# main.net
KiCad netlist of a schematic drawn in EAGLE
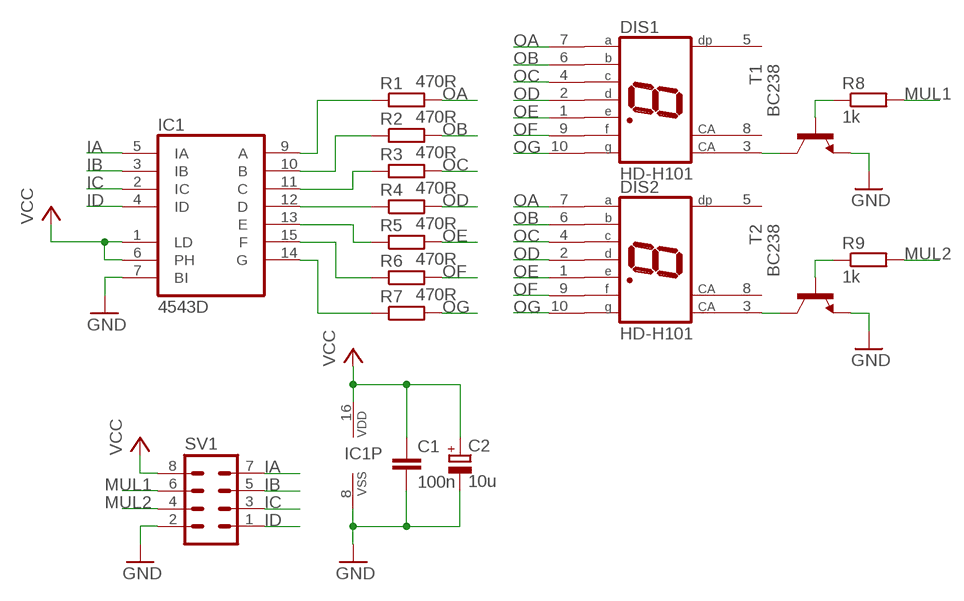
[diagram p0: schematic, sheet 1]

(export (version "E")
  (design (tool "Eeschema 10.0.6"))
  (components
    (comp (ref "C1")
      (value "100n")
      (footprint "eagle-import:C1206")
      (libsource (lib "eagle-import") (part "C-EUC1206"))
    )
    (comp (ref "C2")
      (value "10u")
      (footprint "eagle-import:SMC_A")
      (libsource (lib "eagle-import") (part "CPOL-EUSMCA"))
    )
    (comp (ref "DIS1")
      (value "HD-H101")
      (footprint "eagle-import:HDSP-M")
      (libsource (lib "eagle-import") (part "HD-H101"))
    )
    (comp (ref "DIS2")
      (value "HD-H101")
      (footprint "eagle-import:HDSP-M")
      (libsource (lib "eagle-import") (part "HD-H101"))
    )
    (comp (ref "IC1")
      (value "4543D")
      (footprint "eagle-import:SO16")
      (libsource (lib "eagle-import") (part "4543D"))
    )
    (comp (ref "R1")
      (value "470R")
      (footprint "eagle-import:R1206")
      (libsource (lib "eagle-import") (part "R-EU_R1206"))
    )
    (comp (ref "R2")
      (value "470R")
      (footprint "eagle-import:R1206")
      (libsource (lib "eagle-import") (part "R-EU_R1206"))
    )
    (comp (ref "R3")
      (value "470R")
      (footprint "eagle-import:R1206")
      (libsource (lib "eagle-import") (part "R-EU_R1206"))
    )
    (comp (ref "R4")
      (value "470R")
      (footprint "eagle-import:R1206")
      (libsource (lib "eagle-import") (part "R-EU_R1206"))
    )
    (comp (ref "R5")
      (value "470R")
      (footprint "eagle-import:R1206")
      (libsource (lib "eagle-import") (part "R-EU_R1206"))
    )
    (comp (ref "R6")
      (value "470R")
      (footprint "eagle-import:R1206")
      (libsource (lib "eagle-import") (part "R-EU_R1206"))
    )
    (comp (ref "R7")
      (value "470R")
      (footprint "eagle-import:R1206")
      (libsource (lib "eagle-import") (part "R-EU_R1206"))
    )
    (comp (ref "R8")
      (value "1k")
      (footprint "eagle-import:R1206")
      (libsource (lib "eagle-import") (part "R-EU_R1206"))
    )
    (comp (ref "R9")
      (value "1k")
      (footprint "eagle-import:R1206")
      (libsource (lib "eagle-import") (part "R-EU_R1206"))
    )
    (comp (ref "SV1")
      (value "MA04-2")
      (footprint "eagle-import:MA04-2")
      (libsource (lib "eagle-import") (part "MA04-2"))
    )
    (comp (ref "T1")
      (value "BC238")
      (footprint "eagle-import:TO92")
      (libsource (lib "eagle-import") (part "BC238"))
    )
    (comp (ref "T2")
      (value "BC238")
      (footprint "eagle-import:TO92")
      (libsource (lib "eagle-import") (part "BC238"))
    )
  )
  (nets
    (net (code "1") (name "/IA") (class "Default")
      (node (ref "IC1") (pin "5") (pinfunction "IA_5") (pintype "input"))
      (node (ref "SV1") (pin "7") (pinfunction "7_7") (pintype "passive"))
    )
    (net (code "2") (name "/IB") (class "Default")
      (node (ref "IC1") (pin "3") (pinfunction "IB_3") (pintype "input"))
      (node (ref "SV1") (pin "5") (pinfunction "5_5") (pintype "passive"))
    )
    (net (code "3") (name "/IC") (class "Default")
      (node (ref "IC1") (pin "2") (pinfunction "IC_2") (pintype "input"))
      (node (ref "SV1") (pin "3") (pinfunction "3_3") (pintype "passive"))
    )
    (net (code "4") (name "/ID") (class "Default")
      (node (ref "IC1") (pin "4") (pinfunction "ID_4") (pintype "input"))
      (node (ref "SV1") (pin "1") (pinfunction "1_1") (pintype "passive"))
    )
    (net (code "5") (name "/MUL1") (class "Default")
      (node (ref "R8") (pin "2") (pinfunction "2_2") (pintype "passive"))
      (node (ref "SV1") (pin "6") (pinfunction "6_6") (pintype "passive"))
    )
    (net (code "6") (name "/MUL2") (class "Default")
      (node (ref "R9") (pin "2") (pinfunction "2_2") (pintype "passive"))
      (node (ref "SV1") (pin "4") (pinfunction "4_4") (pintype "passive"))
    )
    (net (code "7") (name "/OA") (class "Default")
      (node (ref "DIS1") (pin "7") (pinfunction "A_7") (pintype "passive"))
      (node (ref "DIS2") (pin "7") (pinfunction "A_7") (pintype "passive"))
      (node (ref "R1") (pin "2") (pinfunction "2_2") (pintype "passive"))
    )
    (net (code "8") (name "/OB") (class "Default")
      (node (ref "DIS1") (pin "6") (pinfunction "B_6") (pintype "passive"))
      (node (ref "DIS2") (pin "6") (pinfunction "B_6") (pintype "passive"))
      (node (ref "R2") (pin "2") (pinfunction "2_2") (pintype "passive"))
    )
    (net (code "9") (name "/OC") (class "Default")
      (node (ref "DIS1") (pin "4") (pinfunction "C_4") (pintype "passive"))
      (node (ref "DIS2") (pin "4") (pinfunction "C_4") (pintype "passive"))
      (node (ref "R3") (pin "2") (pinfunction "2_2") (pintype "passive"))
    )
    (net (code "10") (name "/OD") (class "Default")
      (node (ref "DIS1") (pin "2") (pinfunction "D_2") (pintype "passive"))
      (node (ref "DIS2") (pin "2") (pinfunction "D_2") (pintype "passive"))
      (node (ref "R4") (pin "2") (pinfunction "2_2") (pintype "passive"))
    )
    (net (code "11") (name "/OE") (class "Default")
      (node (ref "DIS1") (pin "1") (pinfunction "E_1") (pintype "passive"))
      (node (ref "DIS2") (pin "1") (pinfunction "E_1") (pintype "passive"))
      (node (ref "R5") (pin "2") (pinfunction "2_2") (pintype "passive"))
    )
    (net (code "12") (name "/OF") (class "Default")
      (node (ref "DIS1") (pin "9") (pinfunction "F_9") (pintype "passive"))
      (node (ref "DIS2") (pin "9") (pinfunction "F_9") (pintype "passive"))
      (node (ref "R6") (pin "2") (pinfunction "2_2") (pintype "passive"))
    )
    (net (code "13") (name "/OG") (class "Default")
      (node (ref "DIS1") (pin "10") (pinfunction "G_10") (pintype "passive"))
      (node (ref "DIS2") (pin "10") (pinfunction "G_10") (pintype "passive"))
      (node (ref "R7") (pin "2") (pinfunction "2_2") (pintype "passive"))
    )
    (net (code "14") (name "GND") (class "Default")
      (node (ref "C1") (pin "2") (pinfunction "2_2") (pintype "passive"))
      (node (ref "C2") (pin "-") (pinfunction "-_-") (pintype "passive"))
      (node (ref "IC1") (pin "7") (pinfunction "BI_7") (pintype "input"))
      (node (ref "IC1") (pin "8") (pinfunction "VSS_8") (pintype "power_in"))
      (node (ref "SV1") (pin "2") (pinfunction "2_2") (pintype "passive"))
      (node (ref "T1") (pin "1") (pinfunction "E_1") (pintype "passive"))
      (node (ref "T2") (pin "1") (pinfunction "E_1") (pintype "passive"))
    )
    (net (code "15") (name "Net-(IC1A-A)") (class "Default")
      (node (ref "IC1") (pin "9") (pinfunction "A_9") (pintype "output"))
      (node (ref "R1") (pin "1") (pinfunction "1_1") (pintype "passive"))
    )
    (net (code "16") (name "Net-(IC1A-B)") (class "Default")
      (node (ref "IC1") (pin "10") (pinfunction "B_10") (pintype "output"))
      (node (ref "R2") (pin "1") (pinfunction "1_1") (pintype "passive"))
    )
    (net (code "17") (name "Net-(IC1A-C)") (class "Default")
      (node (ref "IC1") (pin "11") (pinfunction "C_11") (pintype "output"))
      (node (ref "R3") (pin "1") (pinfunction "1_1") (pintype "passive"))
    )
    (net (code "18") (name "Net-(IC1A-D)") (class "Default")
      (node (ref "IC1") (pin "12") (pinfunction "D_12") (pintype "output"))
      (node (ref "R4") (pin "1") (pinfunction "1_1") (pintype "passive"))
    )
    (net (code "19") (name "Net-(IC1A-E)") (class "Default")
      (node (ref "IC1") (pin "13") (pinfunction "E_13") (pintype "output"))
      (node (ref "R5") (pin "1") (pinfunction "1_1") (pintype "passive"))
    )
    (net (code "20") (name "Net-(IC1A-F)") (class "Default")
      (node (ref "IC1") (pin "15") (pinfunction "F_15") (pintype "output"))
      (node (ref "R6") (pin "1") (pinfunction "1_1") (pintype "passive"))
    )
    (net (code "21") (name "Net-(IC1A-G)") (class "Default")
      (node (ref "IC1") (pin "14") (pinfunction "G_14") (pintype "output"))
      (node (ref "R7") (pin "1") (pinfunction "1_1") (pintype "passive"))
    )
    (net (code "22") (name "Net-(T1-B)") (class "Default")
      (node (ref "R8") (pin "1") (pinfunction "1_1") (pintype "passive"))
      (node (ref "T1") (pin "2") (pinfunction "B_2") (pintype "passive"))
    )
    (net (code "23") (name "Net-(T1-C)") (class "Default")
      (node (ref "DIS1") (pin "3") (pinfunction "CA_3") (pintype "passive"))
      (node (ref "T1") (pin "3") (pinfunction "C_3") (pintype "passive"))
    )
    (net (code "24") (name "Net-(T2-B)") (class "Default")
      (node (ref "R9") (pin "1") (pinfunction "1_1") (pintype "passive"))
      (node (ref "T2") (pin "2") (pinfunction "B_2") (pintype "passive"))
    )
    (net (code "25") (name "Net-(T2-C)") (class "Default")
      (node (ref "DIS2") (pin "3") (pinfunction "CA_3") (pintype "passive"))
      (node (ref "T2") (pin "3") (pinfunction "C_3") (pintype "passive"))
    )
    (net (code "26") (name "VCC") (class "Default")
      (node (ref "C1") (pin "1") (pinfunction "1_1") (pintype "passive"))
      (node (ref "C2") (pin "+") (pinfunction "+_+") (pintype "passive"))
      (node (ref "IC1") (pin "1") (pinfunction "LD_1") (pintype "input"))
      (node (ref "IC1") (pin "16") (pinfunction "VDD_16") (pintype "power_in"))
      (node (ref "IC1") (pin "6") (pinfunction "PH_6") (pintype "input"))
      (node (ref "SV1") (pin "8") (pinfunction "8_8") (pintype "passive"))
    )
    (net (code "27") (name "unconnected-(DIS1-CA-Pad8)") (class "Default")
      (node (ref "DIS1") (pin "8") (pinfunction "CA_8") (pintype "passive"))
    )
    (net (code "28") (name "unconnected-(DIS1-DP-Pad5)") (class "Default")
      (node (ref "DIS1") (pin "5") (pinfunction "DP_5") (pintype "passive"))
    )
    (net (code "29") (name "unconnected-(DIS2-CA-Pad8)") (class "Default")
      (node (ref "DIS2") (pin "8") (pinfunction "CA_8") (pintype "passive"))
    )
    (net (code "30") (name "unconnected-(DIS2-DP-Pad5)") (class "Default")
      (node (ref "DIS2") (pin "5") (pinfunction "DP_5") (pintype "passive"))
    )
  )
)
